# CH32H417MEU6-R0.net
KiCad netlist of a schematic drawn in Altium Designer
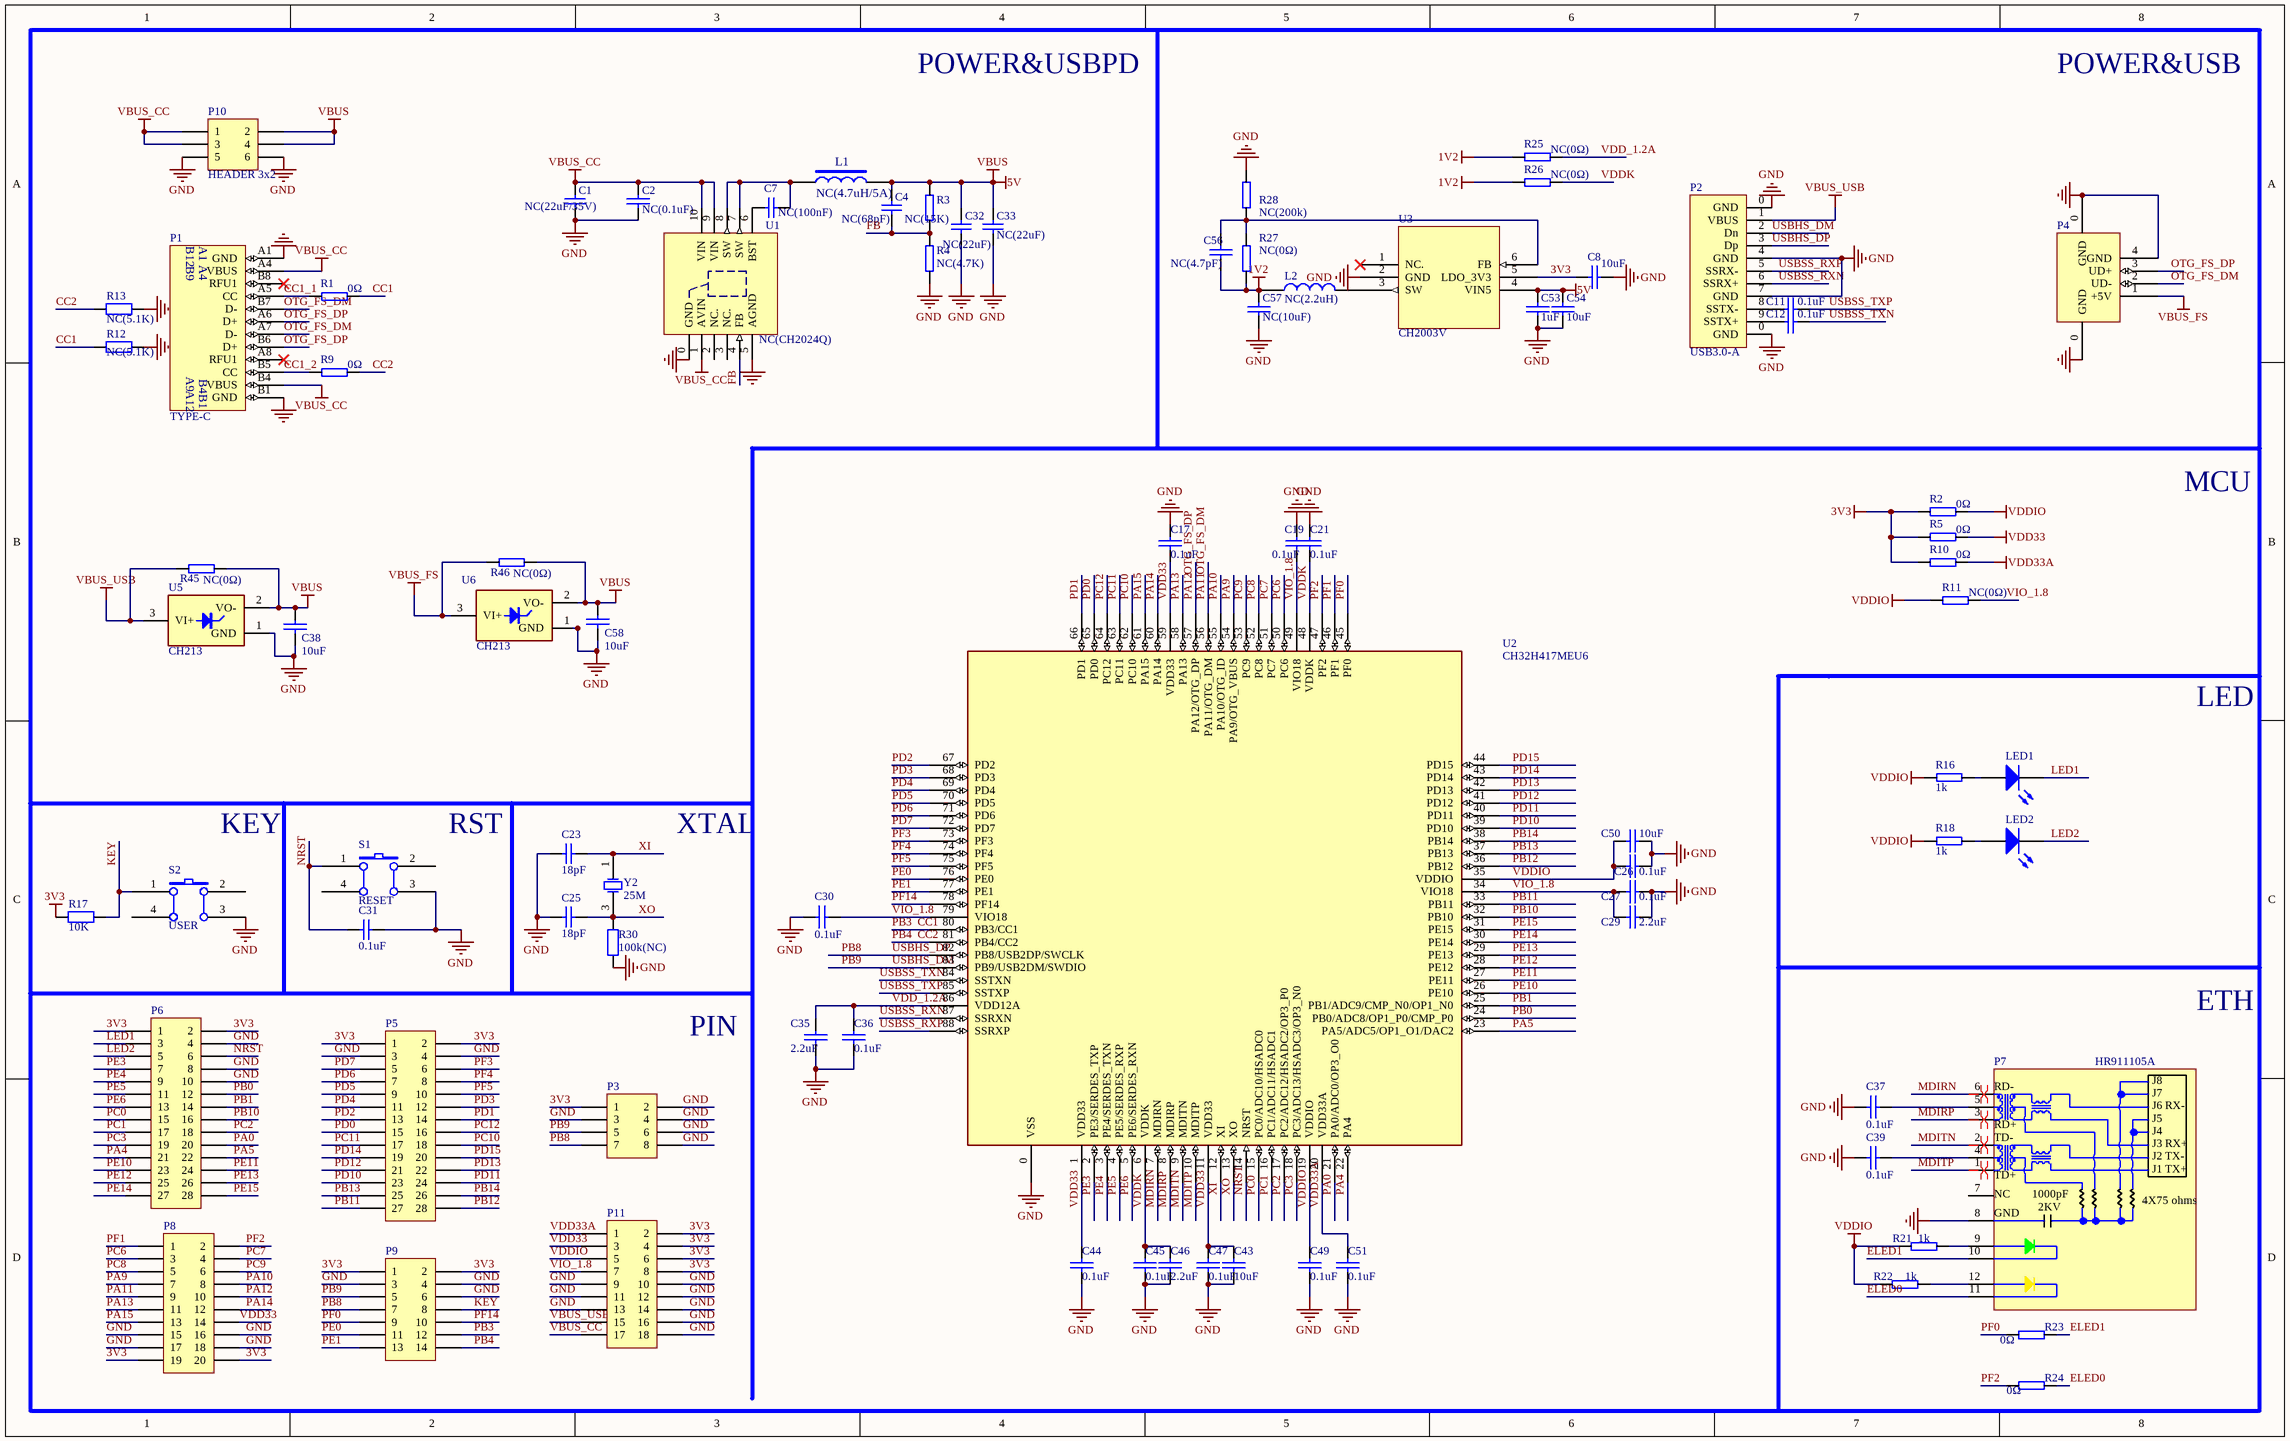
[diagram p0: CH32H417MEU6-R0.SchDoc]

(export (version "E")
  (design (tool "Eeschema 10.0.6"))
  (components
    (comp (ref "C1")
      (value "NC(22uF/35V)")
      (footprint "0805_C")
      (description "贴片电容")
      (libsource (lib "Miscellaneous Devices LC") (part "0603 100nF (104) 10% 50V"))
    )
    (comp (ref "C2")
      (value "NC(0.1uF)")
      (footprint "0402_C")
      (description "Capacitor")
      (libsource (lib "*") (part "CAP"))
    )
    (comp (ref "C4")
      (value "NC(68pF)")
      (footprint "0402_C")
      (description "贴片电容")
      (libsource (lib "Miscellaneous Devices LC") (part "0603 100nF (104) 10% 50V"))
    )
    (comp (ref "C7")
      (value "NC(100nF)")
      (footprint "0603_C")
      (description "贴片电容")
      (libsource (lib "Miscellaneous Devices LC") (part "0603 1uF (105) 10% 50V"))
    )
    (comp (ref "C8")
      (value "10uF")
      (footprint "0603_C")
      (description "Capacitor")
      (libsource (lib "*") (part "CAP"))
    )
    (comp (ref "C11")
      (value "0.1uF")
      (footprint "0402_C")
      (description "Capacitor")
      (libsource (lib "*") (part "CAP"))
    )
    (comp (ref "C12")
      (value "0.1uF")
      (footprint "0402_C")
      (description "Capacitor")
      (libsource (lib "*") (part "CAP"))
    )
    (comp (ref "C17")
      (value "0.1uF")
      (footprint "0402_C")
      (description "Capacitor")
      (libsource (lib "*") (part "CAP"))
    )
    (comp (ref "C19")
      (value "0.1uF")
      (footprint "0402_C")
      (description "Capacitor")
      (libsource (lib "*") (part "CAP"))
    )
    (comp (ref "C21")
      (value "0.1uF")
      (footprint "0402_C")
      (description "Capacitor")
      (libsource (lib "*") (part "CAP"))
    )
    (comp (ref "C23")
      (value "18pF")
      (footprint "0402_C")
      (description "Capacitor")
      (libsource (lib "Miscellaneous Devices") (part "Cap"))
    )
    (comp (ref "C25")
      (value "18pF")
      (footprint "0402_C")
      (description "Capacitor")
      (libsource (lib "Miscellaneous Devices") (part "Cap"))
    )
    (comp (ref "C26")
      (value "0.1uF")
      (footprint "0402_C")
      (description "Capacitor")
      (libsource (lib "*") (part "CAP"))
    )
    (comp (ref "C27")
      (value "0.1uF")
      (footprint "0402_C")
      (description "Capacitor")
      (libsource (lib "*") (part "CAP"))
    )
    (comp (ref "C29")
      (value "2.2uF")
      (footprint "0402_C")
      (description "Capacitor")
      (libsource (lib "*") (part "CAP"))
    )
    (comp (ref "C30")
      (value "0.1uF")
      (footprint "0402_C")
      (description "Capacitor")
      (libsource (lib "*") (part "CAP"))
    )
    (comp (ref "C31")
      (value "0.1uF")
      (footprint "0402_C")
      (description "Capacitor")
      (libsource (lib "Miscellaneous Devices") (part "Cap"))
    )
    (comp (ref "C32")
      (value "NC(22uF)")
      (footprint "0805_C")
      (description "贴片电容")
      (libsource (lib "Miscellaneous Devices LC") (part "0603 100nF (104) 10% 50V"))
    )
    (comp (ref "C33")
      (value "NC(22uF)")
      (footprint "0805_C")
      (description "贴片电容")
      (libsource (lib "Miscellaneous Devices LC") (part "0603 100nF (104) 10% 50V"))
    )
    (comp (ref "C35")
      (value "2.2uF")
      (footprint "0402_C")
      (description "Capacitor")
      (libsource (lib "*") (part "CAP"))
    )
    (comp (ref "C36")
      (value "0.1uF")
      (footprint "0402_C")
      (description "Capacitor")
      (libsource (lib "*") (part "CAP"))
    )
    (comp (ref "C37")
      (value "0.1uF")
      (footprint "0402_C")
      (description "Capacitor")
      (libsource (lib "wch_sch_others") (part "CAP"))
    )
    (comp (ref "C38")
      (value "10uF")
      (footprint "0603_C")
      (description "Capacitor")
      (libsource (lib "") (part "CAP_2"))
    )
    (comp (ref "C39")
      (value "0.1uF")
      (footprint "0402_C")
      (description "Capacitor")
      (libsource (lib "wch_sch_others") (part "CAP"))
    )
    (comp (ref "C43")
      (value "10uF")
      (footprint "0402_C")
      (description "Capacitor")
      (libsource (lib "*") (part "CAP"))
    )
    (comp (ref "C44")
      (value "0.1uF")
      (footprint "0402_C")
      (description "Capacitor")
      (libsource (lib "*") (part "CAP"))
    )
    (comp (ref "C45")
      (value "0.1uF")
      (footprint "0402_C")
      (description "Capacitor")
      (libsource (lib "*") (part "CAP"))
    )
    (comp (ref "C46")
      (value "2.2uF")
      (footprint "0402_C")
      (description "Capacitor")
      (libsource (lib "*") (part "CAP"))
    )
    (comp (ref "C47")
      (value "0.1uF")
      (footprint "0402_C")
      (description "Capacitor")
      (libsource (lib "*") (part "CAP"))
    )
    (comp (ref "C49")
      (value "0.1uF")
      (footprint "0402_C")
      (description "Capacitor")
      (libsource (lib "*") (part "CAP"))
    )
    (comp (ref "C50")
      (value "10uF")
      (footprint "0402_C")
      (description "Capacitor")
      (libsource (lib "*") (part "CAP"))
    )
    (comp (ref "C51")
      (value "0.1uF")
      (footprint "0402_C")
      (description "Capacitor")
      (libsource (lib "*") (part "CAP"))
    )
    (comp (ref "C53")
      (value "1uF")
      (footprint "0402_C")
      (description "Capacitor")
      (libsource (lib "") (part "CAP_1"))
    )
    (comp (ref "C54")
      (value "10uF")
      (footprint "0603_C")
      (description "Capacitor")
      (libsource (lib "*") (part "CAP"))
    )
    (comp (ref "C56")
      (value "NC(4.7pF)")
      (footprint "0402_C")
      (description "Capacitor")
      (libsource (lib "") (part "CAP_1"))
    )
    (comp (ref "C57")
      (value "NC(10uF)")
      (footprint "0603_C")
      (description "Capacitor")
      (libsource (lib "*") (part "CAP"))
    )
    (comp (ref "C58")
      (value "10uF")
      (footprint "0603_C")
      (description "Capacitor")
      (libsource (lib "") (part "CAP_2"))
    )
    (comp (ref "L1")
      (value "NC(4.7uH/5A)")
      (footprint "SMD_6x6mm")
      (libsource (lib "wch_sch_others") (part "INDUCTOR"))
    )
    (comp (ref "L2") (value "NC(2.2uH)") (footprint "CD32") (libsource (lib "*") (part "INDUCTOR")))
    (comp (ref "LED1")
      (value "LED2  blue")
      (footprint "0603+")
      (description "Typical INFRARED GaAs LED")
      (fields (field (name "PUBLISHER") "Altium Limited"))
      (libsource (lib "Miscellaneous Devices") (part "LED0"))
    )
    (comp (ref "LED2")
      (value "LED1   blue")
      (footprint "0603+")
      (description "Typical INFRARED GaAs LED")
      (fields (field (name "PUBLISHER") "Altium Limited"))
      (libsource (lib "Miscellaneous Devices") (part "LED0"))
    )
    (comp (ref "P1")
      (value "TYPE-C")
      (footprint "TYPE-C-Receptacle-2.0")
      (libsource (lib "*") (part "TYPE-C1"))
    )
    (comp (ref "P2")
      (value "USB3.0-A")
      (footprint "USB3.0-A-Receptacle")
      (libsource (lib "wch_sch_others") (part "USB3.0-A"))
    )
    (comp (ref "P3")
      (value "HEADER 4x2")
      (footprint "MYPCB:IDC8-2.54mm")
      (description "Header, 4-Pin, Dual row")
      (libsource (lib "wch_sch_others") (part "HEADER 4x2"))
    )
    (comp (ref "P4")
      (value "USB_A")
      (footprint "USBAF")
      (description "USB Port")
      (libsource (lib "*") (part "USB"))
    )
    (comp (ref "P5")
      (value "HEADER 14x2")
      (footprint "MYPCB:IDC28-2.54MM")
      (description "Header, 14-Pin, Dual row")
      (libsource (lib "wch_sch_others") (part "HEADER 14x2"))
    )
    (comp (ref "P6")
      (value "HEADER 14x2")
      (footprint "MYPCB:IDC28-2.54MM")
      (description "Header, 14-Pin, Dual row")
      (libsource (lib "wch_sch_others") (part "HEADER 14x2"))
    )
    (comp (ref "P7") (value "HR911105A") (footprint "HR911105A") (libsource (lib "*") (part "HR911105A")))
    (comp (ref "P8")
      (value "~")
      (footprint "MYPCB:IDC20-2.54MM")
      (description "Header, 10-Pin, Dual row")
      (libsource (lib "wch_sch_others") (part "HEADER 10x2"))
    )
    (comp (ref "P9")
      (value "~")
      (footprint "MYPCB:IDC14-2.54mm")
      (description "Header, 7-Pin, Dual row")
      (libsource (lib "wch_sch_others") (part "HEADER 7x2"))
    )
    (comp (ref "P10")
      (value "HEADER 3x2")
      (footprint "MYPCB:IDC6-2.54mm")
      (description "Header, 3-Pin, Dual row")
      (libsource (lib "wch_sch_others") (part "HEADER 3x2"))
    )
    (comp (ref "P11")
      (value "HEADER 9x2")
      (footprint "MYPCB:IDC18-2.54MM")
      (description "Header, 9-Pin, Dual row")
      (libsource (lib "wch_sch_others") (part "HEADER 9x2"))
    )
    (comp (ref "R1") (value "0Ω") (footprint "0402") (libsource (lib "wch_sch_others") (part "RES")))
    (comp (ref "R2") (value "0Ω") (footprint "0402") (libsource (lib "wch_sch_others") (part "RES")))
    (comp (ref "R3") (value "NC(15K)") (footprint "0402") (libsource (lib "wch_sch_others(1)") (part "RES")))
    (comp (ref "R4") (value "NC(4.7K)") (footprint "0402") (libsource (lib "wch_sch_others(1)") (part "RES")))
    (comp (ref "R5") (value "0Ω") (footprint "0402") (libsource (lib "wch_sch_others") (part "RES")))
    (comp (ref "R9") (value "0Ω") (footprint "0402") (libsource (lib "wch_sch_others") (part "RES")))
    (comp (ref "R10") (value "0Ω") (footprint "0402") (libsource (lib "wch_sch_others") (part "RES")))
    (comp (ref "R11") (value "NC(0Ω)") (footprint "0402") (libsource (lib "wch_sch_others") (part "RES")))
    (comp (ref "R12")
      (value "NC(5.1K)")
      (footprint "0402")
      (description "Resistor")
      (libsource (lib "Miscellaneous Devices") (part "Res2"))
    )
    (comp (ref "R13")
      (value "NC(5.1K)")
      (footprint "0402")
      (description "Resistor")
      (libsource (lib "Miscellaneous Devices") (part "Res2"))
    )
    (comp (ref "R16") (value "1k") (footprint "0402") (libsource (lib "wch_sch_others") (part "RES")))
    (comp (ref "R17")
      (value "10K")
      (footprint "0402")
      (description "Resistor")
      (libsource (lib "") (part "Res2_2"))
    )
    (comp (ref "R18") (value "1k") (footprint "0402") (libsource (lib "wch_sch_others") (part "RES")))
    (comp (ref "R21") (value "1k") (footprint "0402") (libsource (lib "") (part "RES_1")))
    (comp (ref "R22") (value "1k") (footprint "0402") (libsource (lib "") (part "RES_1")))
    (comp (ref "R23") (value "0Ω") (footprint "0402") (libsource (lib "") (part "RES_1")))
    (comp (ref "R24") (value "0Ω") (footprint "0402") (libsource (lib "") (part "RES_1")))
    (comp (ref "R25") (value "NC(0Ω)") (footprint "0402") (libsource (lib "wch_sch_others") (part "RES")))
    (comp (ref "R26") (value "NC(0Ω)") (footprint "0402") (libsource (lib "wch_sch_others") (part "RES")))
    (comp (ref "R27") (value "NC(0Ω)") (footprint "0402") (libsource (lib "wch_sch_others") (part "RES")))
    (comp (ref "R28") (value "NC(200k)") (footprint "0402") (libsource (lib "wch_sch_others") (part "RES")))
    (comp (ref "R30")
      (value "100k(NC)")
      (footprint "0402")
      (description "Resistor")
      (libsource (lib "") (part "Res2_1"))
    )
    (comp (ref "R45") (value "NC(0Ω)") (footprint "0402") (libsource (lib "") (part "RES_1")))
    (comp (ref "R46") (value "NC(0Ω)") (footprint "0402") (libsource (lib "") (part "RES_1")))
    (comp (ref "S1")
      (value "RESET")
      (footprint "KEYX")
      (description "SE PUSHBUTTON")
      (libsource (lib "Documents") (part "SW PUSHBUTTON"))
    )
    (comp (ref "S2")
      (value "USER")
      (footprint "KEYX")
      (description "SE PUSHBUTTON")
      (libsource (lib "Documents") (part "SW PUSHBUTTON"))
    )
    (comp (ref "U1")
      (value "NC(CH2024Q)")
      (footprint "DFN10_3X3")
      (description "Step-Down DC-DC Converter, 28V input, FB 1.2V, 3A output")
      (libsource (lib "DHXXXSCH") (part "CH2024Q"))
    )
    (comp (ref "U2")
      (value "CH32H417MEU6")
      (footprint "QFN88_10X10")
      (description "RISC-V FPU HD-MCU, 384MHz, USB3.0 & PD, 100M Ethernet, DVP, QSPI, OPA, ADC, DAC")
      (libsource (lib "DHXXXSCH(3)") (part "CH32H417MEU6"))
    )
    (comp (ref "U3")
      (value "CH2003V")
      (footprint "SOT-23-6")
      (description "Step-Down DC-DC Converter, 5V input, FB 0.6V, 800mA output, with LDO 3.3V * 200mA")
      (libsource (lib "DHXXXSCH") (part "CH2003K"))
    )
    (comp (ref "U5")
      (value "CH213")
      (footprint "SOT-23-3")
      (description "Ideal Diode 5V*1A")
      (libsource (lib "CHXXX") (part "CH213E"))
    )
    (comp (ref "U6")
      (value "CH213")
      (footprint "SOT-23-3")
      (description "Ideal Diode 5V*1A")
      (libsource (lib "CHXXX") (part "CH213E"))
    )
    (comp (ref "Y2")
      (value "25M")
      (footprint "XT3225")
      (description "Crystal Oscillator")
      (fields (field (name "PUBLISHER") "Altium Limited"))
      (libsource (lib "Miscellaneous Devices") (part "XTAL"))
    )
  )
  (nets
    (net (code "2") (name "/CC1") (class "Default")
      (node (ref "P9") (pin "12") (pinfunction "12_12") (pintype "passive"))
      (node (ref "R1") (pin "1") (pintype "passive"))
      (node (ref "R12") (pin "1") (pinfunction "1_1") (pintype "passive"))
      (node (ref "U2") (pin "80") (pinfunction "PB3/CC1_80") (pintype "bidirectional"))
    )
    (net (code "3") (name "/CC1_1") (class "Default")
      (node (ref "P1") (pin "A5") (pinfunction "CC_A5") (pintype "bidirectional"))
      (node (ref "R1") (pin "2") (pintype "passive"))
    )
    (net (code "4") (name "/CC1_2") (class "Default")
      (node (ref "P1") (pin "B5") (pinfunction "CC_B5") (pintype "bidirectional"))
      (node (ref "R9") (pin "2") (pintype "passive"))
    )
    (net (code "5") (name "/CC2") (class "Default")
      (node (ref "P9") (pin "14") (pinfunction "14_14") (pintype "passive"))
      (node (ref "R13") (pin "1") (pinfunction "1_1") (pintype "passive"))
      (node (ref "R9") (pin "1") (pintype "passive"))
      (node (ref "U2") (pin "81") (pinfunction "PB4/CC2_81") (pintype "bidirectional"))
    )
    (net (code "6") (name "/ELED0") (class "Default")
      (node (ref "P7") (pin "11") (pintype "passive"))
      (node (ref "R24") (pin "2") (pintype "passive"))
    )
    (net (code "7") (name "/ELED1") (class "Default")
      (node (ref "P7") (pin "10") (pintype "passive"))
      (node (ref "R23") (pin "2") (pintype "passive"))
    )
    (net (code "8") (name "/FB") (class "Default")
      (node (ref "C4") (pin "2") (pinfunction "2_2") (pintype "passive"))
      (node (ref "R3") (pin "1") (pintype "passive"))
      (node (ref "R4") (pin "2") (pintype "passive"))
      (node (ref "U1") (pin "4") (pinfunction "FB_4") (pintype "input"))
    )
    (net (code "9") (name "/KEY") (class "Default")
      (node (ref "P9") (pin "8") (pinfunction "8_8") (pintype "passive"))
      (node (ref "R17") (pin "1") (pinfunction "1_1") (pintype "passive"))
      (node (ref "S2") (pin "1") (pinfunction "A0_1") (pintype "passive"))
    )
    (net (code "10") (name "/LED1") (class "Default")
      (node (ref "LED1") (pin "2") (pinfunction "K_2") (pintype "passive"))
      (node (ref "P6") (pin "3") (pinfunction "3_3") (pintype "passive"))
    )
    (net (code "11") (name "/LED2") (class "Default")
      (node (ref "LED2") (pin "2") (pinfunction "K_2") (pintype "passive"))
      (node (ref "P6") (pin "5") (pinfunction "5_5") (pintype "passive"))
    )
    (net (code "12") (name "/MDIRN") (class "Default")
      (node (ref "P7") (pin "6") (pintype "passive"))
      (node (ref "U2") (pin "7") (pinfunction "MDIRN_7") (pintype "bidirectional"))
    )
    (net (code "13") (name "/MDIRP") (class "Default")
      (node (ref "P7") (pin "3") (pintype "passive"))
      (node (ref "U2") (pin "8") (pinfunction "MDIRP_8") (pintype "bidirectional"))
    )
    (net (code "14") (name "/MDITN") (class "Default")
      (node (ref "P7") (pin "2") (pintype "passive"))
      (node (ref "U2") (pin "9") (pinfunction "MDITN_9") (pintype "bidirectional"))
    )
    (net (code "15") (name "/MDITP") (class "Default")
      (node (ref "P7") (pin "1") (pintype "passive"))
      (node (ref "U2") (pin "10") (pinfunction "MDITP_10") (pintype "bidirectional"))
    )
    (net (code "16") (name "/NRST") (class "Default")
      (node (ref "C31") (pin "2") (pinfunction "2_2") (pintype "passive"))
      (node (ref "P6") (pin "6") (pinfunction "6_6") (pintype "passive"))
      (node (ref "S1") (pin "1") (pinfunction "A0_1") (pintype "passive"))
      (node (ref "U2") (pin "14") (pinfunction "NRST_14") (pintype "input"))
    )
    (net (code "17") (name "/OTG_FS_DM") (class "Default")
      (node (ref "P1") (pin "A7") (pinfunction "D-_A7") (pintype "bidirectional"))
      (node (ref "P1") (pin "B7") (pinfunction "D-_B7") (pintype "bidirectional"))
      (node (ref "P4") (pin "2") (pinfunction "UD-_2") (pintype "bidirectional"))
      (node (ref "P8") (pin "9") (pinfunction "9_9") (pintype "passive"))
      (node (ref "U2") (pin "56") (pinfunction "PA11/OTG_DM_56") (pintype "bidirectional"))
    )
    (net (code "18") (name "/OTG_FS_DP") (class "Default")
      (node (ref "P1") (pin "A6") (pinfunction "D+_A6") (pintype "bidirectional"))
      (node (ref "P1") (pin "B6") (pinfunction "D+_B6") (pintype "bidirectional"))
      (node (ref "P4") (pin "3") (pinfunction "UD+_3") (pintype "bidirectional"))
      (node (ref "P8") (pin "10") (pinfunction "10_10") (pintype "passive"))
      (node (ref "U2") (pin "57") (pinfunction "PA12/OTG_DP_57") (pintype "bidirectional"))
    )
    (net (code "19") (name "/PA0") (class "Default")
      (node (ref "P6") (pin "20") (pinfunction "20_20") (pintype "passive"))
      (node (ref "U2") (pin "21") (pinfunction "PA0/ADC0/OP3_O0_21") (pintype "bidirectional"))
    )
    (net (code "20") (name "/PA4") (class "Default")
      (node (ref "P6") (pin "21") (pinfunction "21_21") (pintype "passive"))
      (node (ref "U2") (pin "22") (pinfunction "PA4_22") (pintype "bidirectional"))
    )
    (net (code "21") (name "/PA5") (class "Default")
      (node (ref "P6") (pin "22") (pinfunction "22_22") (pintype "passive"))
      (node (ref "U2") (pin "23") (pinfunction "PA5/ADC5/OP1_O1/DAC2_23") (pintype "bidirectional"))
    )
    (net (code "22") (name "/PA9") (class "Default")
      (node (ref "P8") (pin "7") (pinfunction "7_7") (pintype "passive"))
      (node (ref "U2") (pin "54") (pinfunction "PA9/OTG_VBUS_54") (pintype "bidirectional"))
    )
    (net (code "23") (name "/PA10") (class "Default")
      (node (ref "P8") (pin "8") (pinfunction "8_8") (pintype "passive"))
      (node (ref "U2") (pin "55") (pinfunction "PA10/OTG_ID_55") (pintype "bidirectional"))
    )
    (net (code "24") (name "/PA13") (class "Default")
      (node (ref "P8") (pin "11") (pinfunction "11_11") (pintype "passive"))
      (node (ref "U2") (pin "58") (pinfunction "PA13_58") (pintype "bidirectional"))
    )
    (net (code "25") (name "/PA14") (class "Default")
      (node (ref "P8") (pin "12") (pinfunction "12_12") (pintype "passive"))
      (node (ref "U2") (pin "60") (pinfunction "PA14_60") (pintype "bidirectional"))
    )
    (net (code "26") (name "/PA15") (class "Default")
      (node (ref "P8") (pin "13") (pinfunction "13_13") (pintype "passive"))
      (node (ref "U2") (pin "61") (pinfunction "PA15_61") (pintype "bidirectional"))
    )
    (net (code "27") (name "/PB0") (class "Default")
      (node (ref "P6") (pin "12") (pinfunction "12_12") (pintype "passive"))
      (node (ref "U2") (pin "24") (pinfunction "PB0/ADC8/OP1_P0/CMP_P0_24") (pintype "bidirectional"))
    )
    (net (code "28") (name "/PB1") (class "Default")
      (node (ref "P6") (pin "14") (pinfunction "14_14") (pintype "passive"))
      (node (ref "U2") (pin "25") (pinfunction "PB1/ADC9/CMP_N0/OP1_N0_25") (pintype "bidirectional"))
    )
    (net (code "29") (name "/PB8") (class "Default")
      (node (ref "P2") (pin "3") (pinfunction "Dp_3") (pintype "passive"))
      (node (ref "P3") (pin "7") (pinfunction "7_7") (pintype "passive"))
      (node (ref "P9") (pin "7") (pinfunction "7_7") (pintype "passive"))
      (node (ref "U2") (pin "82") (pinfunction "PB8/USB2DP/SWCLK_82") (pintype "bidirectional"))
    )
    (net (code "30") (name "/PB9") (class "Default")
      (node (ref "P2") (pin "2") (pinfunction "Dn_2") (pintype "passive"))
      (node (ref "P3") (pin "5") (pinfunction "5_5") (pintype "passive"))
      (node (ref "P9") (pin "5") (pinfunction "5_5") (pintype "passive"))
      (node (ref "U2") (pin "83") (pinfunction "PB9/USB2DM/SWDIO_83") (pintype "bidirectional"))
    )
    (net (code "31") (name "/PB10") (class "Default")
      (node (ref "P6") (pin "16") (pinfunction "16_16") (pintype "passive"))
      (node (ref "U2") (pin "32") (pinfunction "PB10_32") (pintype "bidirectional"))
    )
    (net (code "32") (name "/PB11") (class "Default")
      (node (ref "P5") (pin "27") (pinfunction "27_27") (pintype "passive"))
      (node (ref "U2") (pin "33") (pinfunction "PB11_33") (pintype "bidirectional"))
    )
    (net (code "33") (name "/PB12") (class "Default")
      (node (ref "P5") (pin "28") (pinfunction "28_28") (pintype "passive"))
      (node (ref "U2") (pin "36") (pinfunction "PB12_36") (pintype "bidirectional"))
    )
    (net (code "34") (name "/PB13") (class "Default")
      (node (ref "P5") (pin "25") (pinfunction "25_25") (pintype "passive"))
      (node (ref "U2") (pin "37") (pinfunction "PB13_37") (pintype "bidirectional"))
    )
    (net (code "35") (name "/PB14") (class "Default")
      (node (ref "P5") (pin "26") (pinfunction "26_26") (pintype "passive"))
      (node (ref "U2") (pin "38") (pinfunction "PB14_38") (pintype "bidirectional"))
    )
    (net (code "36") (name "/PC0") (class "Default")
      (node (ref "P6") (pin "15") (pinfunction "15_15") (pintype "passive"))
      (node (ref "U2") (pin "15") (pinfunction "PC0/ADC10/HSADC0_15") (pintype "bidirectional"))
    )
    (net (code "37") (name "/PC1") (class "Default")
      (node (ref "P6") (pin "17") (pinfunction "17_17") (pintype "passive"))
      (node (ref "U2") (pin "16") (pinfunction "PC1/ADC11/HSADC1_16") (pintype "bidirectional"))
    )
    (net (code "38") (name "/PC2") (class "Default")
      (node (ref "P6") (pin "18") (pinfunction "18_18") (pintype "passive"))
      (node (ref "U2") (pin "17") (pinfunction "PC2/ADC12/HSADC2/OP3_P0_17") (pintype "bidirectional"))
    )
    (net (code "39") (name "/PC3") (class "Default")
      (node (ref "P6") (pin "19") (pinfunction "19_19") (pintype "passive"))
      (node (ref "U2") (pin "18") (pinfunction "PC3/ADC13/HSADC3/OP3_N0_18") (pintype "bidirectional"))
    )
    (net (code "40") (name "/PC6") (class "Default")
      (node (ref "P8") (pin "3") (pinfunction "3_3") (pintype "passive"))
      (node (ref "U2") (pin "50") (pinfunction "PC6_50") (pintype "bidirectional"))
    )
    (net (code "41") (name "/PC7") (class "Default")
      (node (ref "P8") (pin "4") (pinfunction "4_4") (pintype "passive"))
      (node (ref "U2") (pin "51") (pinfunction "PC7_51") (pintype "bidirectional"))
    )
    (net (code "42") (name "/PC8") (class "Default")
      (node (ref "P8") (pin "5") (pinfunction "5_5") (pintype "passive"))
      (node (ref "U2") (pin "52") (pinfunction "PC8_52") (pintype "bidirectional"))
    )
    (net (code "43") (name "/PC9") (class "Default")
      (node (ref "P8") (pin "6") (pinfunction "6_6") (pintype "passive"))
      (node (ref "U2") (pin "53") (pinfunction "PC9_53") (pintype "bidirectional"))
    )
    (net (code "44") (name "/PC10") (class "Default")
      (node (ref "P5") (pin "18") (pinfunction "18_18") (pintype "passive"))
      (node (ref "U2") (pin "62") (pinfunction "PC10_62") (pintype "bidirectional"))
    )
    (net (code "45") (name "/PC11") (class "Default")
      (node (ref "P5") (pin "17") (pinfunction "17_17") (pintype "passive"))
      (node (ref "U2") (pin "63") (pinfunction "PC11_63") (pintype "bidirectional"))
    )
    (net (code "46") (name "/PC12") (class "Default")
      (node (ref "P5") (pin "16") (pinfunction "16_16") (pintype "passive"))
      (node (ref "U2") (pin "64") (pinfunction "PC12_64") (pintype "bidirectional"))
    )
    (net (code "47") (name "/PD0") (class "Default")
      (node (ref "P5") (pin "15") (pinfunction "15_15") (pintype "passive"))
      (node (ref "U2") (pin "65") (pinfunction "PD0_65") (pintype "bidirectional"))
    )
    (net (code "48") (name "/PD1") (class "Default")
      (node (ref "P5") (pin "14") (pinfunction "14_14") (pintype "passive"))
      (node (ref "U2") (pin "66") (pinfunction "PD1_66") (pintype "bidirectional"))
    )
    (net (code "49") (name "/PD2") (class "Default")
      (node (ref "P5") (pin "13") (pinfunction "13_13") (pintype "passive"))
      (node (ref "U2") (pin "67") (pinfunction "PD2_67") (pintype "bidirectional"))
    )
    (net (code "50") (name "/PD3") (class "Default")
      (node (ref "P5") (pin "12") (pinfunction "12_12") (pintype "passive"))
      (node (ref "U2") (pin "68") (pinfunction "PD3_68") (pintype "bidirectional"))
    )
    (net (code "51") (name "/PD4") (class "Default")
      (node (ref "P5") (pin "11") (pinfunction "11_11") (pintype "passive"))
      (node (ref "U2") (pin "69") (pinfunction "PD4_69") (pintype "bidirectional"))
    )
    (net (code "52") (name "/PD5") (class "Default")
      (node (ref "P5") (pin "9") (pinfunction "9_9") (pintype "passive"))
      (node (ref "U2") (pin "70") (pinfunction "PD5_70") (pintype "bidirectional"))
    )
    (net (code "53") (name "/PD6") (class "Default")
      (node (ref "P5") (pin "7") (pinfunction "7_7") (pintype "passive"))
      (node (ref "U2") (pin "71") (pinfunction "PD6_71") (pintype "bidirectional"))
    )
    (net (code "54") (name "/PD7") (class "Default")
      (node (ref "P5") (pin "5") (pinfunction "5_5") (pintype "passive"))
      (node (ref "U2") (pin "72") (pinfunction "PD7_72") (pintype "bidirectional"))
    )
    (net (code "55") (name "/PD10") (class "Default")
      (node (ref "P5") (pin "23") (pinfunction "23_23") (pintype "passive"))
      (node (ref "U2") (pin "39") (pinfunction "PD10_39") (pintype "bidirectional"))
    )
    (net (code "56") (name "/PD11") (class "Default")
      (node (ref "P5") (pin "24") (pinfunction "24_24") (pintype "passive"))
      (node (ref "U2") (pin "40") (pinfunction "PD11_40") (pintype "bidirectional"))
    )
    (net (code "57") (name "/PD12") (class "Default")
      (node (ref "P5") (pin "21") (pinfunction "21_21") (pintype "passive"))
      (node (ref "U2") (pin "41") (pinfunction "PD12_41") (pintype "bidirectional"))
    )
    (net (code "58") (name "/PD13") (class "Default")
      (node (ref "P5") (pin "22") (pinfunction "22_22") (pintype "passive"))
      (node (ref "U2") (pin "42") (pinfunction "PD13_42") (pintype "bidirectional"))
    )
    (net (code "59") (name "/PD14") (class "Default")
      (node (ref "P5") (pin "19") (pinfunction "19_19") (pintype "passive"))
      (node (ref "U2") (pin "43") (pinfunction "PD14_43") (pintype "bidirectional"))
    )
    (net (code "60") (name "/PD15") (class "Default")
      (node (ref "P5") (pin "20") (pinfunction "20_20") (pintype "passive"))
      (node (ref "U2") (pin "44") (pinfunction "PD15_44") (pintype "bidirectional"))
    )
    (net (code "61") (name "/PE0") (class "Default")
      (node (ref "P9") (pin "11") (pinfunction "11_11") (pintype "passive"))
      (node (ref "U2") (pin "76") (pinfunction "PE0_76") (pintype "bidirectional"))
    )
    (net (code "62") (name "/PE1") (class "Default")
      (node (ref "P9") (pin "13") (pinfunction "13_13") (pintype "passive"))
      (node (ref "U2") (pin "77") (pinfunction "PE1_77") (pintype "bidirectional"))
    )
    (net (code "63") (name "/PE3") (class "Default")
      (node (ref "P6") (pin "7") (pinfunction "7_7") (pintype "passive"))
      (node (ref "U2") (pin "2") (pinfunction "PE3/SERDES_TXP_2") (pintype "bidirectional"))
    )
    (net (code "64") (name "/PE4") (class "Default")
      (node (ref "P6") (pin "9") (pinfunction "9_9") (pintype "passive"))
      (node (ref "U2") (pin "3") (pinfunction "PE4/SERDES_TXN_3") (pintype "bidirectional"))
    )
    (net (code "65") (name "/PE5") (class "Default")
      (node (ref "P6") (pin "11") (pinfunction "11_11") (pintype "passive"))
      (node (ref "U2") (pin "4") (pinfunction "PE5/SERDES_RXP_4") (pintype "bidirectional"))
    )
    (net (code "66") (name "/PE6") (class "Default")
      (node (ref "P6") (pin "13") (pinfunction "13_13") (pintype "passive"))
      (node (ref "U2") (pin "5") (pinfunction "PE6/SERDES_RXN_5") (pintype "bidirectional"))
    )
    (net (code "67") (name "/PE10") (class "Default")
      (node (ref "P6") (pin "23") (pinfunction "23_23") (pintype "passive"))
      (node (ref "U2") (pin "26") (pinfunction "PE10_26") (pintype "bidirectional"))
    )
    (net (code "68") (name "/PE11") (class "Default")
      (node (ref "P6") (pin "24") (pinfunction "24_24") (pintype "passive"))
      (node (ref "U2") (pin "27") (pinfunction "PE11_27") (pintype "bidirectional"))
    )
    (net (code "69") (name "/PE12") (class "Default")
      (node (ref "P6") (pin "25") (pinfunction "25_25") (pintype "passive"))
      (node (ref "U2") (pin "28") (pinfunction "PE12_28") (pintype "bidirectional"))
    )
    (net (code "70") (name "/PE13") (class "Default")
      (node (ref "P6") (pin "26") (pinfunction "26_26") (pintype "passive"))
      (node (ref "U2") (pin "29") (pinfunction "PE13_29") (pintype "bidirectional"))
    )
    (net (code "71") (name "/PE14") (class "Default")
      (node (ref "P6") (pin "27") (pinfunction "27_27") (pintype "passive"))
      (node (ref "U2") (pin "30") (pinfunction "PE14_30") (pintype "bidirectional"))
    )
    (net (code "72") (name "/PE15") (class "Default")
      (node (ref "P6") (pin "28") (pinfunction "28_28") (pintype "passive"))
      (node (ref "U2") (pin "31") (pinfunction "PE15_31") (pintype "bidirectional"))
    )
    (net (code "73") (name "/PF0") (class "Default")
      (node (ref "P9") (pin "9") (pinfunction "9_9") (pintype "passive"))
      (node (ref "R23") (pin "1") (pintype "passive"))
      (node (ref "U2") (pin "45") (pinfunction "PF0_45") (pintype "bidirectional"))
    )
    (net (code "74") (name "/PF1") (class "Default")
      (node (ref "P8") (pin "1") (pinfunction "1_1") (pintype "passive"))
      (node (ref "U2") (pin "46") (pinfunction "PF1_46") (pintype "bidirectional"))
    )
    (net (code "75") (name "/PF2") (class "Default")
      (node (ref "P8") (pin "2") (pinfunction "2_2") (pintype "passive"))
      (node (ref "R24") (pin "1") (pintype "passive"))
      (node (ref "U2") (pin "47") (pinfunction "PF2_47") (pintype "bidirectional"))
    )
    (net (code "76") (name "/PF3") (class "Default")
      (node (ref "P5") (pin "6") (pinfunction "6_6") (pintype "passive"))
      (node (ref "U2") (pin "73") (pinfunction "PF3_73") (pintype "bidirectional"))
    )
    (net (code "77") (name "/PF4") (class "Default")
      (node (ref "P5") (pin "8") (pinfunction "8_8") (pintype "passive"))
      (node (ref "U2") (pin "74") (pinfunction "PF4_74") (pintype "bidirectional"))
    )
    (net (code "78") (name "/PF5") (class "Default")
      (node (ref "P5") (pin "10") (pinfunction "10_10") (pintype "passive"))
      (node (ref "U2") (pin "75") (pinfunction "PF5_75") (pintype "bidirectional"))
    )
    (net (code "79") (name "/PF14") (class "Default")
      (node (ref "P9") (pin "10") (pinfunction "10_10") (pintype "passive"))
      (node (ref "U2") (pin "78") (pinfunction "PF14_78") (pintype "bidirectional"))
    )
    (net (code "80") (name "/USBSS_RXN") (class "Default")
      (node (ref "P2") (pin "6") (pinfunction "SSRX+_6") (pintype "passive"))
      (node (ref "U2") (pin "87") (pinfunction "SSRXN_87") (pintype "bidirectional"))
    )
    (net (code "81") (name "/USBSS_RXP") (class "Default")
      (node (ref "P2") (pin "5") (pinfunction "SSRX-_5") (pintype "passive"))
      (node (ref "U2") (pin "88") (pinfunction "SSRXP_88") (pintype "bidirectional"))
    )
    (net (code "82") (name "/USBSS_TXN") (class "Default")
      (node (ref "C12") (pin "2") (pinfunction "2_2") (pintype "passive"))
      (node (ref "U2") (pin "84") (pinfunction "SSTXN_84") (pintype "bidirectional"))
    )
    (net (code "83") (name "/USBSS_TXP") (class "Default")
      (node (ref "C11") (pin "2") (pinfunction "2_2") (pintype "passive"))
      (node (ref "U2") (pin "85") (pinfunction "SSTXP_85") (pintype "bidirectional"))
    )
    (net (code "84") (name "/VDDK") (class "Default")
      (node (ref "C21") (pin "1") (pinfunction "1_1") (pintype "passive"))
      (node (ref "C45") (pin "2") (pinfunction "2_2") (pintype "passive"))
      (node (ref "C46") (pin "1") (pinfunction "1_1") (pintype "passive"))
      (node (ref "R26") (pin "1") (pintype "passive"))
      (node (ref "U2") (pin "48") (pinfunction "VDDK_48") (pintype "power_in"))
      (node (ref "U2") (pin "6") (pinfunction "VDDK_6") (pintype "power_in"))
    )
    (net (code "85") (name "/VDD_1.2A") (class "Default")
      (node (ref "C35") (pin "2") (pinfunction "2_2") (pintype "passive"))
      (node (ref "C36") (pin "2") (pinfunction "2_2") (pintype "passive"))
      (node (ref "R25") (pin "1") (pintype "passive"))
      (node (ref "U2") (pin "86") (pinfunction "VDD12A_86") (pintype "power_in"))
    )
    (net (code "86") (name "/VIO_1.8") (class "Default")
      (node (ref "C19") (pin "1") (pinfunction "1_1") (pintype "passive"))
      (node (ref "C27") (pin "1") (pinfunction "1_1") (pintype "passive"))
      (node (ref "C29") (pin "1") (pinfunction "1_1") (pintype "passive"))
      (node (ref "C30") (pin "2") (pinfunction "2_2") (pintype "passive"))
      (node (ref "P11") (pin "7") (pinfunction "7_7") (pintype "passive"))
      (node (ref "R11") (pin "1") (pintype "passive"))
      (node (ref "U2") (pin "34") (pinfunction "VIO18_34") (pintype "power_in"))
      (node (ref "U2") (pin "49") (pinfunction "VIO18_49") (pintype "power_in"))
      (node (ref "U2") (pin "79") (pinfunction "VIO18_79") (pintype "power_in"))
    )
    (net (code "87") (name "/XI") (class "Default")
      (node (ref "C23") (pin "2") (pinfunction "2_2") (pintype "passive"))
      (node (ref "U2") (pin "12") (pinfunction "XI_12") (pintype "bidirectional"))
      (node (ref "Y2") (pin "1") (pinfunction "OSC1_1") (pintype "passive"))
    )
    (net (code "88") (name "/XO") (class "Default")
      (node (ref "C25") (pin "2") (pinfunction "2_2") (pintype "passive"))
      (node (ref "R30") (pin "2") (pinfunction "2_2") (pintype "passive"))
      (node (ref "U2") (pin "13") (pinfunction "XO_13") (pintype "bidirectional"))
      (node (ref "Y2") (pin "3") (pinfunction "OSC2_3") (pintype "passive"))
    )
    (net (code "89") (name "1V2") (class "Default")
      (node (ref "C56") (pin "1") (pinfunction "1_1") (pintype "passive"))
      (node (ref "C57") (pin "2") (pinfunction "2_2") (pintype "passive"))
      (node (ref "L2") (pin "2") (pinfunction "2_2") (pintype "passive"))
      (node (ref "R25") (pin "2") (pintype "passive"))
      (node (ref "R26") (pin "2") (pintype "passive"))
      (node (ref "R27") (pin "1") (pintype "passive"))
    )
    (net (code "90") (name "3V3") (class "Default")
      (node (ref "C8") (pin "2") (pinfunction "2_2") (pintype "passive"))
      (node (ref "P11") (pin "2") (pinfunction "2_2") (pintype "passive"))
      (node (ref "P11") (pin "4") (pinfunction "4_4") (pintype "passive"))
      (node (ref "P11") (pin "6") (pinfunction "6_6") (pintype "passive"))
      (node (ref "P11") (pin "8") (pinfunction "8_8") (pintype "passive"))
      (node (ref "P3") (pin "1") (pinfunction "1_1") (pintype "passive"))
      (node (ref "P5") (pin "1") (pinfunction "1_1") (pintype "passive"))
      (node (ref "P5") (pin "2") (pinfunction "2_2") (pintype "passive"))
      (node (ref "P6") (pin "1") (pinfunction "1_1") (pintype "passive"))
      (node (ref "P6") (pin "2") (pinfunction "2_2") (pintype "passive"))
      (node (ref "P8") (pin "19") (pinfunction "19_19") (pintype "passive"))
      (node (ref "P8") (pin "20") (pinfunction "20_20") (pintype "passive"))
      (node (ref "P9") (pin "1") (pinfunction "1_1") (pintype "passive"))
      (node (ref "P9") (pin "2") (pinfunction "2_2") (pintype "passive"))
      (node (ref "R10") (pin "2") (pintype "passive"))
      (node (ref "R17") (pin "2") (pinfunction "2_2") (pintype "passive"))
      (node (ref "R2") (pin "2") (pintype "passive"))
      (node (ref "R5") (pin "2") (pintype "passive"))
      (node (ref "U3") (pin "5") (pinfunction "LDO_3V3_5") (pintype "power_in"))
    )
    (net (code "91") (name "5V") (class "Default")
      (node (ref "C32") (pin "2") (pinfunction "2_2") (pintype "passive"))
      (node (ref "C33") (pin "2") (pinfunction "2_2") (pintype "passive"))
      (node (ref "C38") (pin "1") (pinfunction "1_1") (pintype "passive"))
      (node (ref "C4") (pin "1") (pinfunction "1_1") (pintype "passive"))
      (node (ref "C53") (pin "2") (pinfunction "2_2") (pintype "passive"))
      (node (ref "C54") (pin "2") (pinfunction "2_2") (pintype "passive"))
      (node (ref "C58") (pin "1") (pinfunction "1_1") (pintype "passive"))
      (node (ref "L1") (pin "2") (pinfunction "2_2") (pintype "passive"))
      (node (ref "P10") (pin "2") (pinfunction "2_2") (pintype "passive"))
      (node (ref "P10") (pin "4") (pinfunction "4_4") (pintype "passive"))
      (node (ref "R3") (pin "2") (pintype "passive"))
      (node (ref "R45") (pin "1") (pintype "passive"))
      (node (ref "R46") (pin "1") (pintype "passive"))
      (node (ref "U3") (pin "4") (pinfunction "VIN5_4") (pintype "power_in"))
      (node (ref "U5") (pin "2") (pinfunction "VO-_2") (pintype "power_in"))
      (node (ref "U6") (pin "2") (pinfunction "VO-_2") (pintype "power_in"))
    )
    (net (code "92") (name "GND") (class "Default")
      (node (ref "C1") (pin "1") (pinfunction "1_1") (pintype "passive"))
      (node (ref "C17") (pin "1") (pinfunction "1_1") (pintype "passive"))
      (node (ref "C19") (pin "2") (pinfunction "2_2") (pintype "passive"))
      (node (ref "C2") (pin "1") (pinfunction "1_1") (pintype "passive"))
      (node (ref "C21") (pin "2") (pinfunction "2_2") (pintype "passive"))
      (node (ref "C23") (pin "1") (pinfunction "1_1") (pintype "passive"))
      (node (ref "C25") (pin "1") (pinfunction "1_1") (pintype "passive"))
      (node (ref "C26") (pin "2") (pinfunction "2_2") (pintype "passive"))
      (node (ref "C27") (pin "2") (pinfunction "2_2") (pintype "passive"))
      (node (ref "C29") (pin "2") (pinfunction "2_2") (pintype "passive"))
      (node (ref "C30") (pin "1") (pinfunction "1_1") (pintype "passive"))
      (node (ref "C31") (pin "1") (pinfunction "1_1") (pintype "passive"))
      (node (ref "C32") (pin "1") (pinfunction "1_1") (pintype "passive"))
      (node (ref "C33") (pin "1") (pinfunction "1_1") (pintype "passive"))
      (node (ref "C35") (pin "1") (pinfunction "1_1") (pintype "passive"))
      (node (ref "C36") (pin "1") (pinfunction "1_1") (pintype "passive"))
      (node (ref "C37") (pin "1") (pinfunction "1_1") (pintype "passive"))
      (node (ref "C38") (pin "2") (pinfunction "2_2") (pintype "passive"))
      (node (ref "C39") (pin "1") (pinfunction "1_1") (pintype "passive"))
      (node (ref "C43") (pin "2") (pinfunction "2_2") (pintype "passive"))
      (node (ref "C44") (pin "1") (pinfunction "1_1") (pintype "passive"))
      (node (ref "C45") (pin "1") (pinfunction "1_1") (pintype "passive"))
      (node (ref "C46") (pin "2") (pinfunction "2_2") (pintype "passive"))
      (node (ref "C47") (pin "2") (pinfunction "2_2") (pintype "passive"))
      (node (ref "C49") (pin "1") (pinfunction "1_1") (pintype "passive"))
      (node (ref "C50") (pin "2") (pinfunction "2_2") (pintype "passive"))
      (node (ref "C51") (pin "1") (pinfunction "1_1") (pintype "passive"))
      (node (ref "C53") (pin "1") (pinfunction "1_1") (pintype "passive"))
      (node (ref "C54") (pin "1") (pinfunction "1_1") (pintype "passive"))
      (node (ref "C57") (pin "1") (pinfunction "1_1") (pintype "passive"))
      (node (ref "C58") (pin "2") (pinfunction "2_2") (pintype "passive"))
      (node (ref "C8") (pin "1") (pinfunction "1_1") (pintype "passive"))
      (node (ref "P1") (pin "A1") (pinfunction "GND_A1") (pintype "bidirectional"))
      (node (ref "P1") (pin "B1") (pinfunction "GND_B1") (pintype "bidirectional"))
      (node (ref "P10") (pin "5") (pinfunction "5_5") (pintype "passive"))
      (node (ref "P10") (pin "6") (pinfunction "6_6") (pintype "passive"))
      (node (ref "P11") (pin "10") (pinfunction "10_10") (pintype "passive"))
      (node (ref "P11") (pin "11") (pinfunction "11_11") (pintype "passive"))
      (node (ref "P11") (pin "12") (pinfunction "12_12") (pintype "passive"))
      (node (ref "P11") (pin "13") (pinfunction "13_13") (pintype "passive"))
      (node (ref "P11") (pin "14") (pinfunction "14_14") (pintype "passive"))
      (node (ref "P11") (pin "16") (pinfunction "16_16") (pintype "passive"))
      (node (ref "P11") (pin "18") (pinfunction "18_18") (pintype "passive"))
      (node (ref "P11") (pin "9") (pinfunction "9_9") (pintype "passive"))
      (node (ref "P2") (pin "0") (pinfunction "GND_0") (pintype "passive"))
      (node (ref "P2") (pin "4") (pinfunction "GND_4") (pintype "passive"))
      (node (ref "P2") (pin "7") (pinfunction "GND_7") (pintype "passive"))
      (node (ref "P3") (pin "2") (pinfunction "2_2") (pintype "passive"))
      (node (ref "P3") (pin "3") (pinfunction "3_3") (pintype "passive"))
      (node (ref "P3") (pin "4") (pinfunction "4_4") (pintype "passive"))
      (node (ref "P3") (pin "6") (pinfunction "6_6") (pintype "passive"))
      (node (ref "P3") (pin "8") (pinfunction "8_8") (pintype "passive"))
      (node (ref "P4") (pin "0") (pinfunction "GND_0") (pintype "power_in"))
      (node (ref "P4") (pin "4") (pinfunction "GND_4") (pintype "power_in"))
      (node (ref "P5") (pin "3") (pinfunction "3_3") (pintype "passive"))
      (node (ref "P5") (pin "4") (pinfunction "4_4") (pintype "passive"))
      (node (ref "P6") (pin "10") (pinfunction "10_10") (pintype "passive"))
      (node (ref "P6") (pin "4") (pinfunction "4_4") (pintype "passive"))
      (node (ref "P6") (pin "8") (pinfunction "8_8") (pintype "passive"))
      (node (ref "P7") (pin "8") (pintype "passive"))
      (node (ref "P8") (pin "15") (pinfunction "15_15") (pintype "passive"))
      (node (ref "P8") (pin "16") (pinfunction "16_16") (pintype "passive"))
      (node (ref "P8") (pin "17") (pinfunction "17_17") (pintype "passive"))
      (node (ref "P8") (pin "18") (pinfunction "18_18") (pintype "passive"))
      (node (ref "P9") (pin "3") (pinfunction "3_3") (pintype "passive"))
      (node (ref "P9") (pin "4") (pinfunction "4_4") (pintype "passive"))
      (node (ref "P9") (pin "6") (pinfunction "6_6") (pintype "passive"))
      (node (ref "R12") (pin "2") (pinfunction "2_2") (pintype "passive"))
      (node (ref "R13") (pin "2") (pinfunction "2_2") (pintype "passive"))
      (node (ref "R28") (pin "2") (pintype "passive"))
      (node (ref "R30") (pin "1") (pinfunction "1_1") (pintype "passive"))
      (node (ref "R4") (pin "1") (pintype "passive"))
      (node (ref "S1") (pin "3") (pinfunction "B1_3") (pintype "passive"))
      (node (ref "S2") (pin "3") (pinfunction "B1_3") (pintype "passive"))
      (node (ref "U1") (pin "0") (pinfunction "GND_0") (pintype "power_in"))
      (node (ref "U1") (pin "5") (pinfunction "AGND_5") (pintype "power_in"))
      (node (ref "U2") (pin "0") (pinfunction "VSS_0") (pintype "power_in"))
      (node (ref "U3") (pin "2") (pinfunction "GND_2") (pintype "power_in"))
      (node (ref "U5") (pin "1") (pinfunction "GND_1") (pintype "power_in"))
      (node (ref "U6") (pin "1") (pinfunction "GND_1") (pintype "power_in"))
    )
    (net (code "93") (name "Net-(C7-Pad2)") (class "Default")
      (node (ref "C7") (pin "2") (pinfunction "2_2") (pintype "passive"))
      (node (ref "L1") (pin "1") (pinfunction "1_1") (pintype "passive"))
      (node (ref "U1") (pin "7") (pinfunction "SW_7") (pintype "output"))
      (node (ref "U1") (pin "8") (pinfunction "SW_8") (pintype "output"))
    )
    (net (code "94") (name "Net-(C37-Pad2)") (class "Default")
      (node (ref "C37") (pin "2") (pinfunction "2_2") (pintype "passive"))
      (node (ref "P7") (pin "5") (pintype "passive"))
    )
    (net (code "95") (name "Net-(C39-Pad2)") (class "Default")
      (node (ref "C39") (pin "2") (pinfunction "2_2") (pintype "passive"))
      (node (ref "P7") (pin "4") (pintype "passive"))
    )
    (net (code "96") (name "Net-(LED1-A)") (class "Default")
      (node (ref "LED1") (pin "1") (pinfunction "A_1") (pintype "passive"))
      (node (ref "R16") (pin "2") (pintype "passive"))
    )
    (net (code "97") (name "Net-(LED2-A)") (class "Default")
      (node (ref "LED2") (pin "1") (pinfunction "A_1") (pintype "passive"))
      (node (ref "R18") (pin "2") (pintype "passive"))
    )
    (net (code "98") (name "Net-(P2-SSTX+)") (class "Default")
      (node (ref "C12") (pin "1") (pinfunction "1_1") (pintype "passive"))
      (node (ref "P2") (pin "9") (pinfunction "SSTX+_9") (pintype "passive"))
    )
    (net (code "99") (name "Net-(P2-SSTX-)") (class "Default")
      (node (ref "C11") (pin "1") (pinfunction "1_1") (pintype "passive"))
      (node (ref "P2") (pin "8") (pinfunction "SSTX-_8") (pintype "passive"))
    )
    (net (code "100") (name "Net-(P7-Pad9)") (class "Default")
      (node (ref "P7") (pin "9") (pintype "passive"))
      (node (ref "R21") (pin "2") (pintype "passive"))
    )
    (net (code "101") (name "Net-(P7-Pad12)") (class "Default")
      (node (ref "P7") (pin "12") (pintype "passive"))
      (node (ref "R22") (pin "2") (pintype "passive"))
    )
    (net (code "102") (name "Net-(U1-BST)") (class "Default")
      (node (ref "C7") (pin "1") (pinfunction "1_1") (pintype "passive"))
      (node (ref "U1") (pin "6") (pinfunction "BST_6") (pintype "power_in"))
    )
    (net (code "103") (name "Net-(U3-FB)") (class "Default")
      (node (ref "C56") (pin "2") (pinfunction "2_2") (pintype "passive"))
      (node (ref "R27") (pin "2") (pintype "passive"))
      (node (ref "R28") (pin "1") (pintype "passive"))
      (node (ref "U3") (pin "6") (pinfunction "FB_6") (pintype "input"))
    )
    (net (code "104") (name "Net-(U3-SW)") (class "Default")
      (node (ref "L2") (pin "1") (pinfunction "1_1") (pintype "passive"))
      (node (ref "U3") (pin "3") (pinfunction "SW_3") (pintype "output"))
    )
    (net (code "105") (name "VBUS_CC") (class "Default")
      (node (ref "C1") (pin "2") (pinfunction "2_2") (pintype "passive"))
      (node (ref "C2") (pin "2") (pinfunction "2_2") (pintype "passive"))
      (node (ref "P1") (pin "A4") (pinfunction "VBUS_A4") (pintype "bidirectional"))
      (node (ref "P1") (pin "B4") (pinfunction "VBUS_B4") (pintype "bidirectional"))
      (node (ref "P10") (pin "1") (pinfunction "1_1") (pintype "passive"))
      (node (ref "P10") (pin "3") (pinfunction "3_3") (pintype "passive"))
      (node (ref "P11") (pin "17") (pinfunction "17_17") (pintype "passive"))
      (node (ref "U1") (pin "1") (pinfunction "AVIN_1") (pintype "power_in"))
      (node (ref "U1") (pin "10") (pinfunction "VIN_10") (pintype "power_in"))
      (node (ref "U1") (pin "9") (pinfunction "VIN_9") (pintype "power_in"))
    )
    (net (code "106") (name "VBUS_FS") (class "Default")
      (node (ref "P4") (pin "1") (pinfunction "+5V_1") (pintype "power_in"))
      (node (ref "R46") (pin "2") (pintype "passive"))
      (node (ref "U6") (pin "3") (pinfunction "VI+_3") (pintype "power_in"))
    )
    (net (code "107") (name "VBUS_USB") (class "Default")
      (node (ref "P11") (pin "15") (pinfunction "15_15") (pintype "passive"))
      (node (ref "P2") (pin "1") (pinfunction "VBUS_1") (pintype "passive"))
      (node (ref "R45") (pin "2") (pintype "passive"))
      (node (ref "U5") (pin "3") (pinfunction "VI+_3") (pintype "power_in"))
    )
    (net (code "108") (name "VDD33") (class "Default")
      (node (ref "C17") (pin "2") (pinfunction "2_2") (pintype "passive"))
      (node (ref "C43") (pin "1") (pinfunction "1_1") (pintype "passive"))
      (node (ref "C44") (pin "2") (pinfunction "2_2") (pintype "passive"))
      (node (ref "C47") (pin "1") (pinfunction "1_1") (pintype "passive"))
      (node (ref "P11") (pin "3") (pinfunction "3_3") (pintype "passive"))
      (node (ref "P8") (pin "14") (pinfunction "14_14") (pintype "passive"))
      (node (ref "R5") (pin "1") (pintype "passive"))
      (node (ref "U2") (pin "1") (pinfunction "VDD33_1") (pintype "power_in"))
      (node (ref "U2") (pin "11") (pinfunction "VDD33_11") (pintype "power_in"))
      (node (ref "U2") (pin "59") (pinfunction "VDD33_59") (pintype "power_in"))
    )
    (net (code "109") (name "VDD33A") (class "Default")
      (node (ref "C51") (pin "2") (pinfunction "2_2") (pintype "passive"))
      (node (ref "P11") (pin "1") (pinfunction "1_1") (pintype "passive"))
      (node (ref "R10") (pin "1") (pintype "passive"))
      (node (ref "U2") (pin "20") (pinfunction "VDD33A_20") (pintype "power_in"))
    )
    (net (code "110") (name "VDDIO") (class "Default")
      (node (ref "C26") (pin "1") (pinfunction "1_1") (pintype "passive"))
      (node (ref "C49") (pin "2") (pinfunction "2_2") (pintype "passive"))
      (node (ref "C50") (pin "1") (pinfunction "1_1") (pintype "passive"))
      (node (ref "P11") (pin "5") (pinfunction "5_5") (pintype "passive"))
      (node (ref "R11") (pin "2") (pintype "passive"))
      (node (ref "R16") (pin "1") (pintype "passive"))
      (node (ref "R18") (pin "1") (pintype "passive"))
      (node (ref "R2") (pin "1") (pintype "passive"))
      (node (ref "R21") (pin "1") (pintype "passive"))
      (node (ref "R22") (pin "1") (pintype "passive"))
      (node (ref "U2") (pin "19") (pinfunction "VDDIO_19") (pintype "power_in"))
      (node (ref "U2") (pin "35") (pinfunction "VDDIO_35") (pintype "power_in"))
    )
    (net (code "111") (name "unconnected-(P1-RFU1-PadA8)") (class "Default")
      (node (ref "P1") (pin "A8") (pinfunction "RFU1_A8") (pintype "bidirectional+no_connect"))
    )
    (net (code "112") (name "unconnected-(P1-RFU1-PadB8)") (class "Default")
      (node (ref "P1") (pin "B8") (pinfunction "RFU1_B8") (pintype "bidirectional+no_connect"))
    )
    (net (code "113") (name "unconnected-(P7-Pad7)") (class "Default")
      (node (ref "P7") (pin "7") (pintype "passive"))
    )
    (net (code "114") (name "unconnected-(S1-A1-Pad4)") (class "Default")
      (node (ref "S1") (pin "4") (pinfunction "A1_4") (pintype "passive"))
    )
    (net (code "115") (name "unconnected-(S1-B0-Pad2)") (class "Default")
      (node (ref "S1") (pin "2") (pinfunction "B0_2") (pintype "passive"))
    )
    (net (code "116") (name "unconnected-(S2-A1-Pad4)") (class "Default")
      (node (ref "S2") (pin "4") (pinfunction "A1_4") (pintype "passive"))
    )
    (net (code "117") (name "unconnected-(S2-B0-Pad2)") (class "Default")
      (node (ref "S2") (pin "2") (pinfunction "B0_2") (pintype "passive"))
    )
    (net (code "118") (name "unconnected-(U1-NC.-Pad2)") (class "Default")
      (node (ref "U1") (pin "2") (pinfunction "NC._2") (pintype "passive"))
    )
    (net (code "119") (name "unconnected-(U1-NC.-Pad3)") (class "Default")
      (node (ref "U1") (pin "3") (pinfunction "NC._3") (pintype "passive"))
    )
    (net (code "120") (name "unconnected-(U3-NC.-Pad1)") (class "Default")
      (node (ref "U3") (pin "1") (pinfunction "NC._1") (pintype "passive+no_connect"))
    )
  )
)
